# supply_unit.net
KiCad netlist of a schematic drawn in Altium Designer
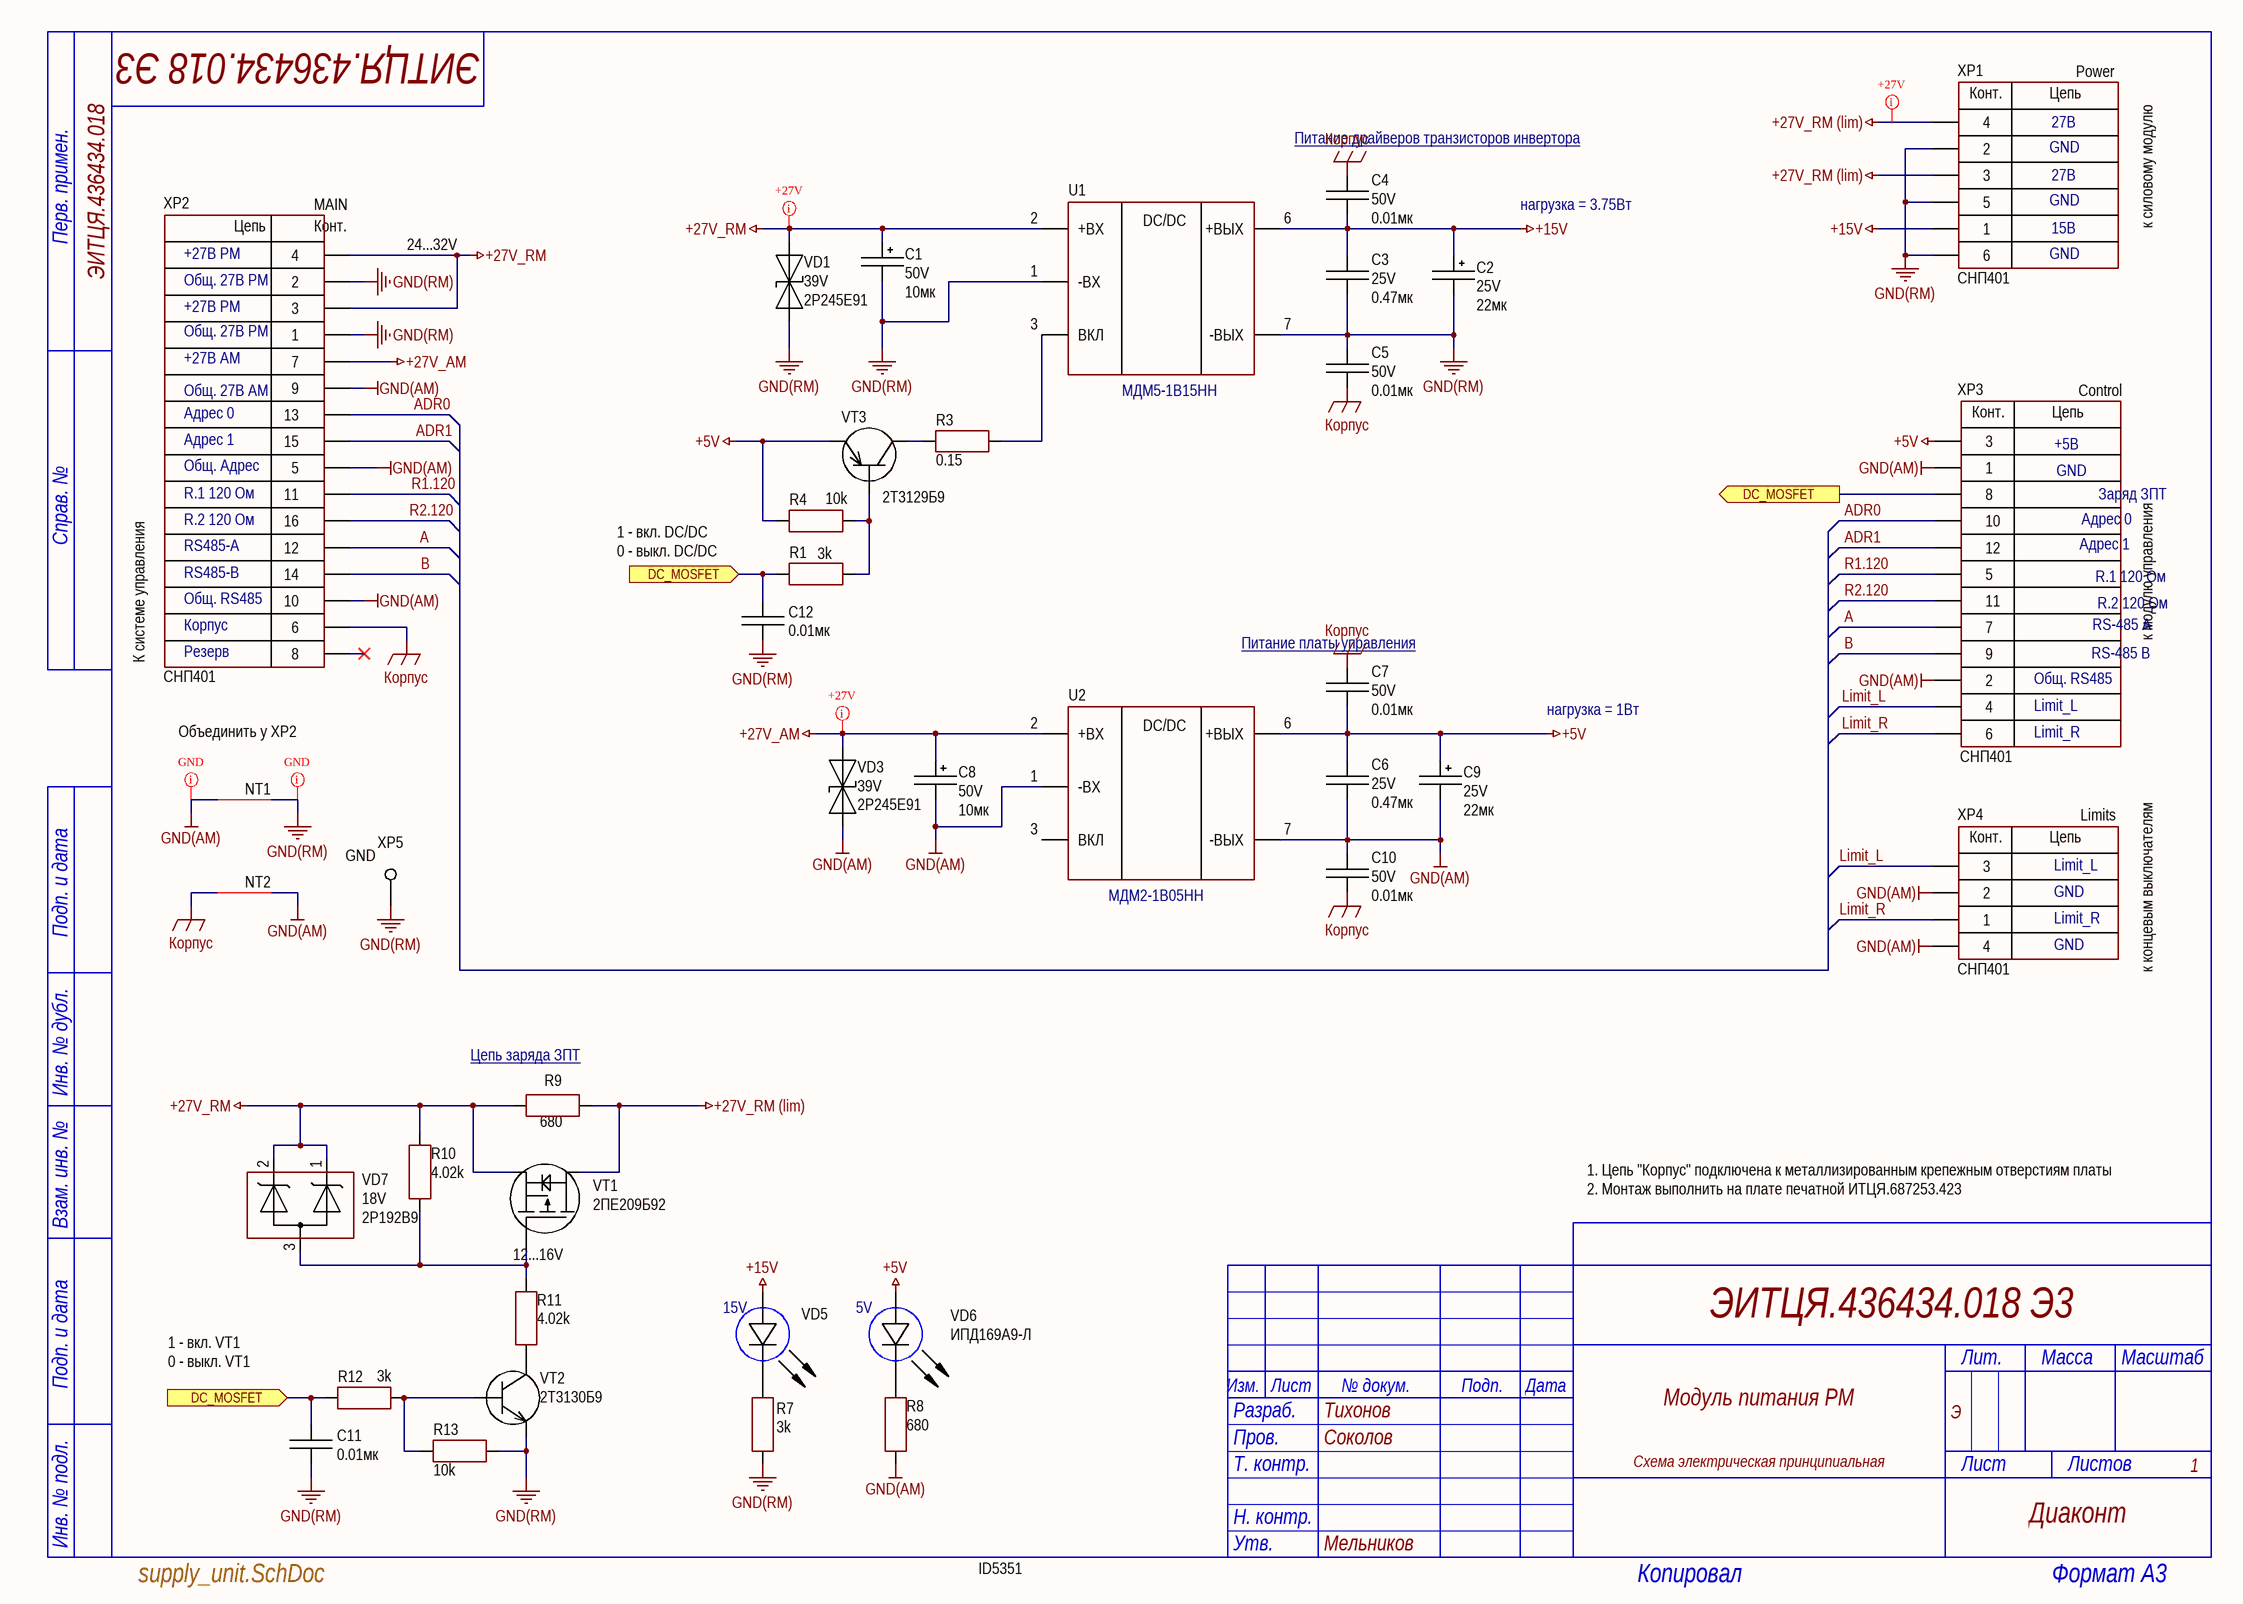
[diagram p0: supply_unit.SchDoc]

(export (version "E")
  (design (tool "Eeschema 10.0.6"))
  (components
    (comp (ref "C1")
      (value "10мк")
      (footprint "StandardCase:CAP: TANTAL-E")
      (fields
        (field (name "MANUFACTURER") "Элеконд")
        (field (name "PARTNUMBER") "К53-68 \"E\"-50 В-10мкф ±10%")
        (field (name "VALUEMANUFACTURERPARTNUMBER") "Tantalum capacitor, 10мк, 50V, ±10%, 0.7 Ом, case E, -60...+125°C")
        (field (name "VOLTAGE") "50V")
      )
      (libsource (lib "Capacitor") (part "Tantal_E"))
    )
    (comp (ref "C2")
      (value "22мк")
      (footprint "StandardCase:CAP: TANTAL-D")
      (fields
        (field (name "MANUFACTURER") "Элеконд")
        (field (name "PARTNUMBER") "К53-68 \"D\"-25 В-22мкф ±10%")
        (field (name "VALUEMANUFACTURERPARTNUMBER") "Tantalum capacitor, 22мк, 25V, ±10%, 0.7 Ом, case D, -60...+125°C")
        (field (name "VOLTAGE") "25V")
      )
      (libsource (lib "Capacitor") (part "Tantal_D"))
    )
    (comp (ref "C3")
      (value "0.47мк")
      (footprint "StandardCase:CAP: 1210")
      (fields
        (field (name "MANUFACTURER") "Монолит")
        (field (name "PARTNUMBER") "К10-84в-3225М-25В-0,47 мкФ ±10%-Н20-N-A")
        (field (name "VALUEMANUFACTURERPARTNUMBER") "Ceramic capacitor, 0.47мк, Н20, ±10%, 25V, 1210 (3225М), ")
        (field (name "VOLTAGE") "25V")
      )
      (libsource (lib "Capacitor") (part "Ceramic_0603"))
    )
    (comp (ref "C4")
      (value "0.01мк")
      (footprint "StandardCase:CAP: 0603")
      (fields
        (field (name "MANUFACTURER") "Монолит")
        (field (name "PARTNUMBER") "К10-84в-1608М-50В-0.01мк ±20%-Н20-N-A")
        (field (name "VALUEMANUFACTURERPARTNUMBER") "Ceramic capacitor, 0.01мк, Н20, ±10%, 50V, 0603 (1608M), -55...+125°C")
        (field (name "VOLTAGE") "50V")
      )
      (libsource (lib "Capacitor") (part "Ceramic_0603"))
    )
    (comp (ref "C5")
      (value "0.01мк")
      (footprint "StandardCase:CAP: 0603")
      (fields
        (field (name "MANUFACTURER") "Монолит")
        (field (name "PARTNUMBER") "К10-84в-1608М-50В-0.01мк ±20%-Н20-N-A")
        (field (name "VALUEMANUFACTURERPARTNUMBER") "Ceramic capacitor, 0.01мк, Н20, ±10%, 50V, 0603 (1608M), -55...+125°C")
        (field (name "VOLTAGE") "50V")
      )
      (libsource (lib "Capacitor") (part "Ceramic_0603"))
    )
    (comp (ref "C6")
      (value "0.47мк")
      (footprint "StandardCase:CAP: 1210")
      (fields
        (field (name "MANUFACTURER") "Монолит")
        (field (name "PARTNUMBER") "К10-84в-3225М-25В-0,47 мкФ ±10%-Н20-N-A")
        (field (name "VALUEMANUFACTURERPARTNUMBER") "Ceramic capacitor, 0.47мк, Н20, ±10%, 25V, 1210 (3225М), ")
        (field (name "VOLTAGE") "25V")
      )
      (libsource (lib "Capacitor") (part "Ceramic_0603"))
    )
    (comp (ref "C7")
      (value "0.01мк")
      (footprint "StandardCase:CAP: 0603")
      (fields
        (field (name "MANUFACTURER") "Монолит")
        (field (name "PARTNUMBER") "К10-84в-1608М-50В-0.01мк ±20%-Н20-N-A")
        (field (name "VALUEMANUFACTURERPARTNUMBER") "Ceramic capacitor, 0.01мк, Н20, ±10%, 50V, 0603 (1608M), -55...+125°C")
        (field (name "VOLTAGE") "50V")
      )
      (libsource (lib "Capacitor") (part "Ceramic_0603"))
    )
    (comp (ref "C8")
      (value "10мк")
      (footprint "StandardCase:CAP: TANTAL-E")
      (fields
        (field (name "MANUFACTURER") "Элеконд")
        (field (name "PARTNUMBER") "К53-68 \"E\"-50 В-10мкф ±10%")
        (field (name "VALUEMANUFACTURERPARTNUMBER") "Tantalum capacitor, 10мк, 50V, ±10%, 0.7 Ом, case E, -60...+125°C")
        (field (name "VOLTAGE") "50V")
      )
      (libsource (lib "Capacitor") (part "Tantal_E"))
    )
    (comp (ref "C9")
      (value "22мк")
      (footprint "StandardCase:CAP: TANTAL-D")
      (fields
        (field (name "MANUFACTURER") "Элеконд")
        (field (name "PARTNUMBER") "К53-68 \"D\"-25 В-22мкф ±10%")
        (field (name "VALUEMANUFACTURERPARTNUMBER") "Tantalum capacitor, 22мк, 25V, ±10%, 0.7 Ом, case D, -60...+125°C")
        (field (name "VOLTAGE") "25V")
      )
      (libsource (lib "Capacitor") (part "Tantal_D"))
    )
    (comp (ref "C10")
      (value "0.01мк")
      (footprint "StandardCase:CAP: 0603")
      (fields
        (field (name "MANUFACTURER") "Монолит")
        (field (name "PARTNUMBER") "К10-84в-1608М-50В-0.01мк ±20%-Н20-N-A")
        (field (name "VALUEMANUFACTURERPARTNUMBER") "Ceramic capacitor, 0.01мк, Н20, ±10%, 50V, 0603 (1608M), -55...+125°C")
        (field (name "VOLTAGE") "50V")
      )
      (libsource (lib "Capacitor") (part "Ceramic_0603"))
    )
    (comp (ref "C11")
      (value "0.01мк")
      (footprint "StandardCase:CAP: 0603P")
      (fields
        (field (name "MANUFACTURER") "Монолит")
        (field (name "PARTNUMBER") "К10-84в-1608М-50В-0.01мк ±20%-Н20-N-A")
        (field (name "VALUEMANUFACTURERPARTNUMBER") "Ceramic capacitor, 0.01мк, H20, ±20%, 50V, 0603 (1608M), -55...+125°C")
      )
      (libsource (lib "") (part "Ceramic_0603_1"))
    )
    (comp (ref "C12")
      (value "0.01мк")
      (footprint "StandardCase:CAP: 0603P")
      (fields
        (field (name "MANUFACTURER") "Монолит")
        (field (name "PARTNUMBER") "К10-84в-1608М-50В-0.01мк ±20%-Н20-N-A")
        (field (name "VALUEMANUFACTURERPARTNUMBER") "Ceramic capacitor, 0.01мк, H20, ±20%, 50V, 0603 (1608M), -55...+125°C")
      )
      (libsource (lib "") (part "Ceramic_0603_1"))
    )
    (comp (ref "NT1")
      (value "~")
      (footprint "CustomCase:NetTie_0805")
      (libsource (lib "Connector") (part "NetTie"))
    )
    (comp (ref "NT2")
      (value "~")
      (footprint "CustomCase:NetTie_0603")
      (libsource (lib "Connector") (part "NetTie"))
    )
    (comp (ref "R1")
      (value "3k")
      (footprint "RES: 0603P")
      (fields
        (field (name "MANUFACTURER") "ОАО Ресурс")
        (field (name "PARTNUMBER") "Р1-12-0,1ум.-3~кОм ±5%-М ШКАБ.434110.002 ТУ")
        (field (name "VALUEMANUFACTURERPARTNUMBER") "Resistor film, 3k, ±1%, 0603, 0.1W, -55...+125°C")
      )
      (libsource (lib "") (part "Resistor_0603_2"))
    )
    (comp (ref "R3")
      (value "0.15")
      (footprint "RES: 0603P")
      (fields
        (field (name "MANUFACTURER") "ОАО Ресурс")
        (field (name "PARTNUMBER") "Р1-12-0,1ум.-0.15~Ом ±20%-М ШКАБ.434110.002 ТУ")
        (field (name "VALUEMANUFACTURERPARTNUMBER") "Resistor film, 0.15, ±20%, 0603, 0.1W, -55...+125°C")
      )
      (libsource (lib "Resistor") (part "Resistor_0603"))
    )
    (comp (ref "R4")
      (value "10k")
      (footprint "RES: 0603P")
      (fields
        (field (name "MANUFACTURER") "ОАО Ресурс")
        (field (name "PARTNUMBER") "Р1-12-0,1ум.-10~кОм ±5%-М ШКАБ.434110.002 ТУ")
        (field (name "VALUEMANUFACTURERPARTNUMBER") "Resistor film, 10k, ±5%, 0603, 0.1W, -55...+125°C")
      )
      (libsource (lib "") (part "Resistor_0603_1"))
    )
    (comp (ref "R7")
      (value "3k")
      (footprint "RES: 0603P")
      (fields
        (field (name "MANUFACTURER") "ОАО Ресурс")
        (field (name "PARTNUMBER") "Р1-12-0,1ум.-3~кОм ±5%-М ШКАБ.434110.002 ТУ")
        (field (name "VALUEMANUFACTURERPARTNUMBER") "Resistor film, 3k, ±1%, 0603, 0.1W, -55...+125°C")
      )
      (libsource (lib "") (part "Resistor_0603_1"))
    )
    (comp (ref "R8")
      (value "680")
      (footprint "RES: 0603P")
      (fields
        (field (name "MANUFACTURER") "ОАО Ресурс")
        (field (name "PARTNUMBER") "Р1-12-0,1ум.-680~Ом ±5%-М ШКАБ.434110.002 ТУ")
        (field (name "VALUEMANUFACTURERPARTNUMBER") "Resistor film, 680, ±5%, 0603, 0.1W, -55...+125°C")
      )
      (libsource (lib "") (part "Resistor_0603_2"))
    )
    (comp (ref "R9")
      (value "680")
      (footprint "StandardCase:RES: 0805P")
      (fields
        (field (name "MANUFACTURER") "Ресурс")
        (field (name "PARTNUMBER") "Р1-12-0,125-680 Ом ±5%-М ШКАБ.434110.002 ТУ")
        (field (name "VALUEMANUFACTURERPARTNUMBER") "Resistor film, 680, ±5%, 0805, 0.125W, ")
      )
      (libsource (lib "Resistor") (part "Resistor_0805"))
    )
    (comp (ref "R10")
      (value "4.02k")
      (footprint "RES: 0805P")
      (fields
        (field (name "MANUFACTURER") "ОАО Ресурс")
        (field (name "PARTNUMBER") "Р1-12-0,1ум.-4.02~кОм ±1%-М ШКАБ.434110.002 ТУ")
        (field (name "VALUEMANUFACTURERPARTNUMBER") "Resistor film, 4.02k, ±1%, 0805, 0.125W, -55...+125°C")
      )
      (libsource (lib "") (part "Resistor_0603_2"))
    )
    (comp (ref "R11")
      (value "4.02k")
      (footprint "RES: 0805P")
      (fields
        (field (name "MANUFACTURER") "ОАО Ресурс")
        (field (name "PARTNUMBER") "Р1-12-0,1ум.-4.02~кОм ±1%-М ШКАБ.434110.002 ТУ")
        (field (name "VALUEMANUFACTURERPARTNUMBER") "Resistor film, 4.02k, ±1%, 0805, 0.125W, -55...+125°C")
      )
      (libsource (lib "") (part "Resistor_0603_2"))
    )
    (comp (ref "R12")
      (value "3k")
      (footprint "RES: 0603P")
      (fields
        (field (name "MANUFACTURER") "ОАО Ресурс")
        (field (name "PARTNUMBER") "Р1-12-0,1ум.-3~кОм ±5%-М ШКАБ.434110.002 ТУ")
        (field (name "VALUEMANUFACTURERPARTNUMBER") "Resistor film, 3k, ±1%, 0603, 0.1W, -55...+125°C")
      )
      (libsource (lib "Resistor") (part "Resistor_0603"))
    )
    (comp (ref "R13")
      (value "10k")
      (footprint "RES: 0603P")
      (fields
        (field (name "MANUFACTURER") "ОАО Ресурс")
        (field (name "PARTNUMBER") "Р1-12-0,1ум.-10~кОм ±5%-М ШКАБ.434110.002 ТУ")
        (field (name "VALUEMANUFACTURERPARTNUMBER") "Resistor film, 10k, ±5%, 0603, 0.1W, -55...+125°C")
      )
      (libsource (lib "") (part "Resistor_0603_3"))
    )
    (comp (ref "U1")
      (value "~")
      (footprint "StandardCase:SIP-8")
      (description "DC/DC converter")
      (fields
        (field (name "MANUFACTURER") "Aedon")
        (field (name "VALUEMANUFACTURERPARTNUMBER") "DC/DC converter, isolator, 15V 1.5A, -40...+90°C, SIP-8")
        (field (name "COMMENTTEXT") "МДМ5-1В15НН")
      )
      (libsource (lib "Module") (part "МДМ3-1В09СН"))
    )
    (comp (ref "U2")
      (value "~")
      (footprint "StandardCase:SIP-8")
      (description "DC/DC converter")
      (fields
        (field (name "MANUFACTURER") "Aedon")
        (field (name "VALUEMANUFACTURERPARTNUMBER") "DC/DC converter, isolator, 5V 600mA, -40...+90°C, SIP-8")
        (field (name "COMMENTTEXT") "МДМ2-1В05НН")
      )
      (libsource (lib "Module") (part "МДМ3-1В09СН"))
    )
    (comp (ref "VD1")
      (value "~")
      (footprint "StandardCase:DIODE: SMB")
      (fields
        (field (name "MANUFACTURER") "НЗПП")
        (field (name "VALUEMANUFACTURERPARTNUMBER") "Zener diode, 39V, 8A, 0.9V, , SMB(КД-42), ")
        (field (name "VOLTAGE") "39V")
        (field (name "PARTNUMBER") "2Р245Е91")
      )
      (libsource (lib "Diode") (part "TVS_single"))
    )
    (comp (ref "VD3")
      (value "~")
      (footprint "StandardCase:DIODE: SMB")
      (fields
        (field (name "MANUFACTURER") "НЗПП")
        (field (name "VALUEMANUFACTURERPARTNUMBER") "Zener diode, 39V, 8A, 0.9V, , SMB(КД-42), ")
        (field (name "VOLTAGE") "39V")
        (field (name "PARTNUMBER") "2Р245Е91")
      )
      (libsource (lib "Diode") (part "TVS_single"))
    )
    (comp (ref "VD5")
      (value "~")
      (footprint "StandardCase:LED: 0603G")
      (fields
        (field (name "MANUFACTURER") "Протон")
        (field (name "VALUEMANUFACTURERPARTNUMBER") "LED, 20mA max, 1.9V@4mA, 1608, -55...+150°C")
        (field (name "PARTNUMBER") "ИПД169А9-Л")
        (field (name "COMMENTTEXT") "15V")
      )
      (libsource (lib "Diode") (part "LED_single"))
    )
    (comp (ref "VD6")
      (value "~")
      (footprint "StandardCase:LED: 0603G")
      (fields
        (field (name "MANUFACTURER") "Протон")
        (field (name "VALUEMANUFACTURERPARTNUMBER") "LED, 20mA max, 1.9V@4mA, 1608, -55...+150°C")
        (field (name "PARTNUMBER") "ИПД169А9-Л")
        (field (name "COMMENTTEXT") "5V")
      )
      (libsource (lib "Diode") (part "LED_single"))
    )
    (comp (ref "VD7")
      (value "~")
      (footprint "StandardCase:SOT23")
      (fields
        (field (name "MANUFACTURER") "КРИП")
        (field (name "VALUEMANUFACTURERPARTNUMBER") "TVS diode, 18V, 1A, , , SOT-23, -55...+150°C")
        (field (name "VOLTAGE") "18V")
        (field (name "PARTNUMBER") "2Р192В9")
      )
      (libsource (lib "Diode") (part "TVS_array_var2"))
    )
    (comp (ref "VT1")
      (value "~")
      (footprint "StandardCase:DPAK")
      (fields (field (name "MANUFACTURER") "Ангстрем") (field (name "PARTNUMBER") "2ПЕ209Б92"))
      (libsource (lib "Transistor") (part "MOSFET_P_132"))
    )
    (comp (ref "VT2")
      (value "~")
      (footprint "SOT23")
      (fields
        (field (name "MANUFACTURER") "ООО НПК Далекс")
        (field (name "VALUEMANUFACTURERPARTNUMBER") "NPN transistor, 30V, 100mA, , 300mW, 0.7V, 500, SOT-23 (КТ-46), -55...+125°C")
        (field (name "PARTNUMBER") "2Т3130Б9")
      )
      (libsource (lib "Transistor") (part "BJT_NPN_132"))
    )
    (comp (ref "VT3")
      (value "~")
      (footprint "StandardCase:SOT23")
      (fields
        (field (name "VALUEMANUFACTURERPARTNUMBER") "NPN transistor, 40V, 100mA, , 200mW, 1.3V, 220, SOT-23 (КТ-46), ")
        (field (name "PARTNUMBER") "2Т3129Б9")
      )
      (libsource (lib "Transistor") (part "BJT_PNP_123"))
    )
    (comp (ref "XP1")
      (value "~")
      (footprint "CON: M80-5000605")
      (description "вилка на плату")
      (fields
        (field (name "MANUFACTURER") "Электроделать")
        (field (name "VALUEMANUFACTURERPARTNUMBER") "Вилка, 6pin, 2mm, 120VAC, 1.5A")
        (field (name "COMMENTTEXT") "СНП401")
      )
      (libsource (lib "Connector") (part "M80-5000605 Harwin"))
    )
    (comp (ref "XP2")
      (value "~")
      (footprint "CustomCase:CON: M80-5001605")
      (description "вилка на плату")
      (fields
        (field (name "MANUFACTURER") "Электродеталь")
        (field (name "VALUEMANUFACTURERPARTNUMBER") ", 16pin, 2mm, 120VAC, 1.5A")
        (field (name "COMMENTTEXT") "СНП401")
      )
      (libsource (lib "Connector") (part "M80-5001205 Harwin_1"))
    )
    (comp (ref "XP3")
      (value "~")
      (footprint "CustomCase:CON: M80-5001205")
      (description "вилка на плату")
      (fields
        (field (name "MANUFACTURER") "Электродеталь")
        (field (name "VALUEMANUFACTURERPARTNUMBER") "Вилка, 12pin, 2mm, 100V, 1.5A")
        (field (name "COMMENTTEXT") "СНП401")
      )
      (libsource (lib "Connector") (part "M80-5001205 Harwin"))
    )
    (comp (ref "XP4")
      (value "~")
      (footprint "CON: M80-5000405")
      (description "вилка на плату")
      (fields
        (field (name "MANUFACTURER") "Электродеталь")
        (field (name "VALUEMANUFACTURERPARTNUMBER") "Вилка, 4pin, 2mm, 120VAC, 1.5A")
        (field (name "COMMENTTEXT") "СНП401")
      )
      (libsource (lib "Connector") (part "M80-5000405 Harwin"))
    )
    (comp (ref "XP5")
      (value "GND")
      (footprint "CON: PLS2-1")
      (description "Test probe")
      (fields
        (field (name "PARTNUMBER") "СНП377-1ВП21-1")
        (field (name "MANUFACTURER") "Электродеталь")
        (field (name "PUBLISHER") "TEN")
      )
      (libsource (lib "Connector") (part "PLS2-1"))
    )
  )
  (nets
    (net (code "1") (name "+5V") (class "Default")
      (node (ref "C6") (pin "2") (pinfunction "2_2") (pintype "passive"))
      (node (ref "C7") (pin "1") (pinfunction "1_1") (pintype "passive"))
      (node (ref "C9") (pin "1") (pinfunction "1_1") (pintype "power_in"))
      (node (ref "R4") (pin "1") (pinfunction "1_1") (pintype "passive"))
      (node (ref "U2") (pin "6") (pinfunction "+ВЫХ_6") (pintype "power_in"))
      (node (ref "VD6") (pin "1") (pinfunction "A_1") (pintype "passive"))
      (node (ref "VT3") (pin "2") (pinfunction "E_2") (pintype "passive"))
      (node (ref "XP3") (pin "3") (pinfunction "3_3") (pintype "passive"))
    )
    (net (code "2") (name "+15V") (class "Default")
      (node (ref "C2") (pin "1") (pinfunction "1_1") (pintype "power_in"))
      (node (ref "C3") (pin "2") (pinfunction "2_2") (pintype "passive"))
      (node (ref "C4") (pin "1") (pinfunction "1_1") (pintype "passive"))
      (node (ref "U1") (pin "6") (pinfunction "+ВЫХ_6") (pintype "power_in"))
      (node (ref "VD5") (pin "1") (pinfunction "A_1") (pintype "passive"))
      (node (ref "XP1") (pin "1") (pinfunction "1_1") (pintype "passive"))
    )
    (net (code "3") (name "+27V_AM") (class "Default")
      (node (ref "C8") (pin "1") (pinfunction "1_1") (pintype "power_in"))
      (node (ref "U2") (pin "2") (pinfunction "+ВХ_2") (pintype "power_in"))
      (node (ref "VD3") (pin "2") (pinfunction "C_2") (pintype "passive"))
      (node (ref "XP2") (pin "7") (pinfunction "7_7") (pintype "passive"))
    )
    (net (code "4") (name "+27V_RM") (class "Default")
      (node (ref "C1") (pin "1") (pinfunction "1_1") (pintype "power_in"))
      (node (ref "R10") (pin "1") (pinfunction "1_1") (pintype "passive"))
      (node (ref "R9") (pin "1") (pinfunction "1_1") (pintype "passive"))
      (node (ref "U1") (pin "2") (pinfunction "+ВХ_2") (pintype "power_in"))
      (node (ref "VD1") (pin "2") (pinfunction "C_2") (pintype "passive"))
      (node (ref "VD7") (pin "1") (pinfunction "K1_1") (pintype "passive"))
      (node (ref "VD7") (pin "2") (pinfunction "K2_2") (pintype "passive"))
      (node (ref "VT1") (pin "2") (pinfunction "S_2") (pintype "passive"))
      (node (ref "XP2") (pin "3") (pinfunction "3_3") (pintype "passive"))
      (node (ref "XP2") (pin "4") (pinfunction "4_4") (pintype "passive"))
    )
    (net (code "5") (name "+27V_RM (lim)") (class "Default")
      (node (ref "R9") (pin "2") (pinfunction "2_2") (pintype "passive"))
      (node (ref "VT1") (pin "3") (pinfunction "D_3") (pintype "passive"))
      (node (ref "XP1") (pin "3") (pinfunction "3_3") (pintype "passive"))
      (node (ref "XP1") (pin "4") (pinfunction "4_4") (pintype "passive"))
    )
    (net (code "6") (name "/A") (class "Default")
      (node (ref "XP2") (pin "12") (pinfunction "12_12") (pintype "passive"))
      (node (ref "XP3") (pin "7") (pinfunction "7_7") (pintype "passive"))
    )
    (net (code "7") (name "/ADR0") (class "Default")
      (node (ref "XP2") (pin "13") (pinfunction "13_13") (pintype "passive"))
      (node (ref "XP3") (pin "10") (pinfunction "10_10") (pintype "passive"))
    )
    (net (code "8") (name "/ADR1") (class "Default")
      (node (ref "XP2") (pin "15") (pinfunction "15_15") (pintype "passive"))
      (node (ref "XP3") (pin "12") (pinfunction "12_12") (pintype "passive"))
    )
    (net (code "9") (name "/B") (class "Default")
      (node (ref "XP2") (pin "14") (pinfunction "14_14") (pintype "passive"))
      (node (ref "XP3") (pin "9") (pinfunction "9_9") (pintype "passive"))
    )
    (net (code "10") (name "/DC_MOSFET") (class "Default")
      (node (ref "C11") (pin "1") (pinfunction "1_1") (pintype "passive"))
      (node (ref "C12") (pin "1") (pinfunction "1_1") (pintype "passive"))
      (node (ref "R1") (pin "2") (pinfunction "2_2") (pintype "passive"))
      (node (ref "R12") (pin "1") (pinfunction "1_1") (pintype "passive"))
      (node (ref "XP3") (pin "8") (pinfunction "8_8") (pintype "passive"))
    )
    (net (code "11") (name "/Limit_L") (class "Default")
      (node (ref "XP3") (pin "4") (pinfunction "4_4") (pintype "passive"))
      (node (ref "XP4") (pin "3") (pinfunction "3_3") (pintype "passive"))
    )
    (net (code "12") (name "/Limit_R") (class "Default")
      (node (ref "XP3") (pin "6") (pinfunction "6_6") (pintype "passive"))
      (node (ref "XP4") (pin "1") (pinfunction "1_1") (pintype "passive"))
    )
    (net (code "13") (name "/R1.120") (class "Default")
      (node (ref "XP2") (pin "11") (pinfunction "11_11") (pintype "passive"))
      (node (ref "XP3") (pin "5") (pinfunction "5_5") (pintype "passive"))
    )
    (net (code "14") (name "/R2.120") (class "Default")
      (node (ref "XP2") (pin "16") (pinfunction "16_16") (pintype "passive"))
      (node (ref "XP3") (pin "11") (pinfunction "11_11") (pintype "passive"))
    )
    (net (code "15") (name "GND(AM)") (class "Default")
      (node (ref "C10") (pin "2") (pinfunction "2_2") (pintype "passive"))
      (node (ref "C6") (pin "1") (pinfunction "1_1") (pintype "passive"))
      (node (ref "C8") (pin "2") (pinfunction "2_2") (pintype "power_in"))
      (node (ref "C9") (pin "2") (pinfunction "2_2") (pintype "power_in"))
      (node (ref "NT1") (pin "1") (pinfunction "1_1") (pintype "passive"))
      (node (ref "NT2") (pin "2") (pinfunction "2_2") (pintype "passive"))
      (node (ref "R8") (pin "2") (pinfunction "2_2") (pintype "passive"))
      (node (ref "U2") (pin "1") (pinfunction "-ВХ_1") (pintype "power_in"))
      (node (ref "U2") (pin "7") (pinfunction "-ВЫХ_7") (pintype "power_in"))
      (node (ref "VD3") (pin "1") (pinfunction "A_1") (pintype "passive"))
      (node (ref "XP2") (pin "10") (pinfunction "10_10") (pintype "passive"))
      (node (ref "XP2") (pin "5") (pinfunction "5_5") (pintype "passive"))
      (node (ref "XP2") (pin "9") (pinfunction "9_9") (pintype "passive"))
      (node (ref "XP3") (pin "1") (pinfunction "1_1") (pintype "passive"))
      (node (ref "XP3") (pin "2") (pinfunction "2_2") (pintype "passive"))
      (node (ref "XP4") (pin "2") (pinfunction "2_2") (pintype "passive"))
      (node (ref "XP4") (pin "4") (pinfunction "4_4") (pintype "passive"))
    )
    (net (code "16") (name "GND(RM)") (class "Default")
      (node (ref "C1") (pin "2") (pinfunction "2_2") (pintype "power_in"))
      (node (ref "C11") (pin "2") (pinfunction "2_2") (pintype "power_in"))
      (node (ref "C12") (pin "2") (pinfunction "2_2") (pintype "power_in"))
      (node (ref "C2") (pin "2") (pinfunction "2_2") (pintype "power_in"))
      (node (ref "C3") (pin "1") (pinfunction "1_1") (pintype "passive"))
      (node (ref "C5") (pin "2") (pinfunction "2_2") (pintype "passive"))
      (node (ref "NT1") (pin "2") (pinfunction "2_2") (pintype "passive"))
      (node (ref "R13") (pin "1") (pinfunction "1_1") (pintype "passive"))
      (node (ref "R7") (pin "1") (pinfunction "1_1") (pintype "passive"))
      (node (ref "U1") (pin "1") (pinfunction "-ВХ_1") (pintype "power_in"))
      (node (ref "U1") (pin "7") (pinfunction "-ВЫХ_7") (pintype "power_in"))
      (node (ref "VD1") (pin "1") (pinfunction "A_1") (pintype "passive"))
      (node (ref "VT2") (pin "2") (pinfunction "E_2") (pintype "passive"))
      (node (ref "XP1") (pin "2") (pinfunction "2_2") (pintype "passive"))
      (node (ref "XP1") (pin "5") (pinfunction "5_5") (pintype "passive"))
      (node (ref "XP1") (pin "6") (pinfunction "6_6") (pintype "passive"))
      (node (ref "XP2") (pin "1") (pinfunction "1_1") (pintype "passive"))
      (node (ref "XP2") (pin "2") (pinfunction "2_2") (pintype "passive"))
      (node (ref "XP5") (pin "1") (pinfunction "1_1") (pintype "passive"))
    )
    (net (code "17") (name "Net-(U1-ВКЛ)") (class "Default")
      (node (ref "R3") (pin "2") (pinfunction "2_2") (pintype "passive"))
      (node (ref "U1") (pin "3") (pinfunction "ВКЛ_3") (pintype "power_in"))
    )
    (net (code "18") (name "Net-(VD5-C)") (class "Default")
      (node (ref "R7") (pin "2") (pinfunction "2_2") (pintype "passive"))
      (node (ref "VD5") (pin "2") (pinfunction "C_2") (pintype "passive"))
    )
    (net (code "19") (name "Net-(VD6-C)") (class "Default")
      (node (ref "R8") (pin "1") (pinfunction "1_1") (pintype "passive"))
      (node (ref "VD6") (pin "2") (pinfunction "C_2") (pintype "passive"))
    )
    (net (code "20") (name "Net-(VD7-A)") (class "Default")
      (node (ref "R10") (pin "2") (pinfunction "2_2") (pintype "passive"))
      (node (ref "R11") (pin "1") (pinfunction "1_1") (pintype "passive"))
      (node (ref "VD7") (pin "3") (pinfunction "A_3") (pintype "passive"))
      (node (ref "VT1") (pin "1") (pinfunction "G_1") (pintype "passive"))
    )
    (net (code "21") (name "Net-(VT2-B)") (class "Default")
      (node (ref "R12") (pin "2") (pinfunction "2_2") (pintype "passive"))
      (node (ref "R13") (pin "2") (pinfunction "2_2") (pintype "passive"))
      (node (ref "VT2") (pin "1") (pinfunction "B_1") (pintype "passive"))
    )
    (net (code "22") (name "Net-(VT2-C)") (class "Default")
      (node (ref "R11") (pin "2") (pinfunction "2_2") (pintype "passive"))
      (node (ref "VT2") (pin "3") (pinfunction "C_3") (pintype "passive"))
    )
    (net (code "23") (name "Net-(VT3-B)") (class "Default")
      (node (ref "R1") (pin "1") (pinfunction "1_1") (pintype "passive"))
      (node (ref "R4") (pin "2") (pinfunction "2_2") (pintype "passive"))
      (node (ref "VT3") (pin "1") (pinfunction "B_1") (pintype "passive"))
    )
    (net (code "24") (name "Net-(VT3-C)") (class "Default")
      (node (ref "R3") (pin "1") (pinfunction "1_1") (pintype "passive"))
      (node (ref "VT3") (pin "3") (pinfunction "C_3") (pintype "passive"))
    )
    (net (code "25") (name "unconnected-(U2-ВКЛ-Pad3)") (class "Default")
      (node (ref "U2") (pin "3") (pinfunction "ВКЛ_3") (pintype "power_in"))
    )
    (net (code "26") (name "unconnected-(XP2-Pad8)") (class "Default")
      (node (ref "XP2") (pin "8") (pinfunction "8_8") (pintype "passive+no_connect"))
    )
    (net (code "27") (name "Корпус") (class "Default")
      (node (ref "C10") (pin "1") (pinfunction "1_1") (pintype "passive"))
      (node (ref "C4") (pin "2") (pinfunction "2_2") (pintype "passive"))
      (node (ref "C5") (pin "1") (pinfunction "1_1") (pintype "passive"))
      (node (ref "C7") (pin "2") (pinfunction "2_2") (pintype "passive"))
      (node (ref "NT2") (pin "1") (pinfunction "1_1") (pintype "passive"))
      (node (ref "XP2") (pin "6") (pinfunction "6_6") (pintype "passive"))
    )
  )
)
